# PHOTODIODE_SENSOR_NEW.net
KiCad netlist of a schematic drawn in EAGLE
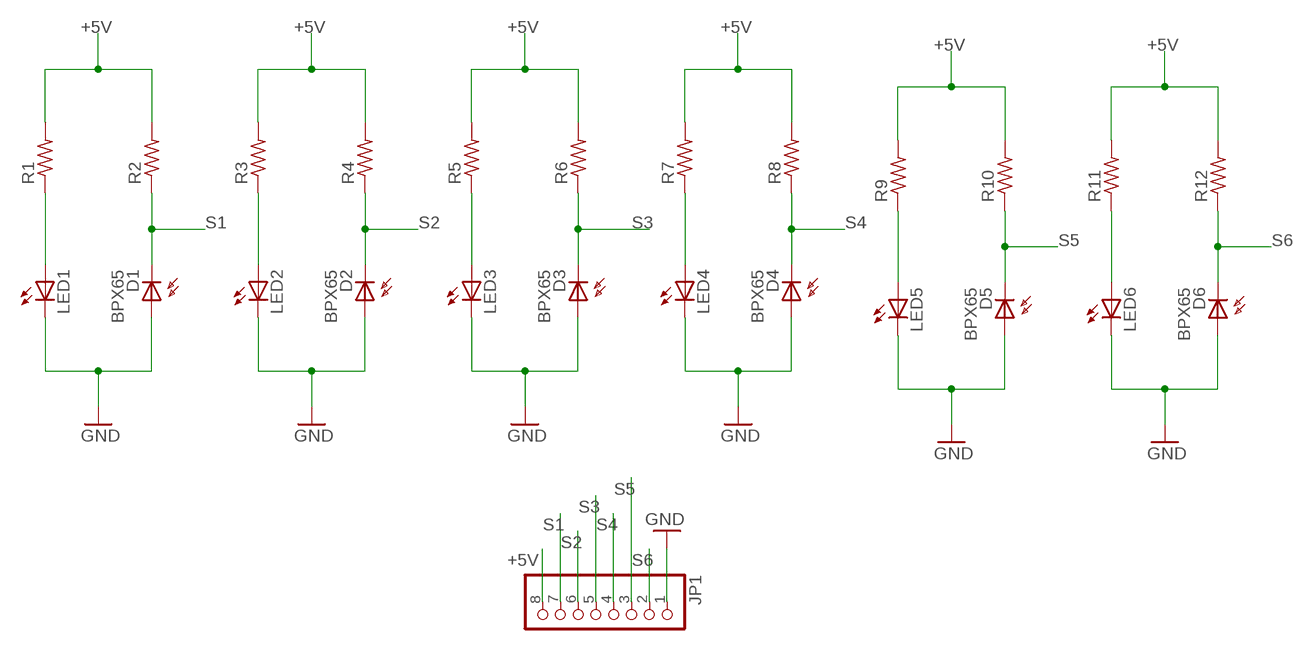
[diagram p0: schematic, sheet 1]

(export (version "E")
  (design (tool "Eeschema 10.0.6"))
  (components
    (comp (ref "D1")
      (value "BPX65")
      (footprint "eagle-import:BPX65")
      (fields (field (name "MPN") "BPX65."))
      (libsource (lib "eagle-import") (part "BPX65"))
    )
    (comp (ref "D2")
      (value "BPX65")
      (footprint "eagle-import:BPX65")
      (fields (field (name "MPN") "BPX65."))
      (libsource (lib "eagle-import") (part "BPX65"))
    )
    (comp (ref "D3")
      (value "BPX65")
      (footprint "eagle-import:BPX65")
      (fields (field (name "MPN") "BPX65."))
      (libsource (lib "eagle-import") (part "BPX65"))
    )
    (comp (ref "D4")
      (value "BPX65")
      (footprint "eagle-import:BPX65")
      (fields (field (name "MPN") "BPX65."))
      (libsource (lib "eagle-import") (part "BPX65"))
    )
    (comp (ref "D5")
      (value "BPX65")
      (footprint "eagle-import:BPX65")
      (fields (field (name "MPN") "BPX65."))
      (libsource (lib "eagle-import") (part "BPX65"))
    )
    (comp (ref "D6")
      (value "BPX65")
      (footprint "eagle-import:BPX65")
      (fields (field (name "MPN") "BPX65."))
      (libsource (lib "eagle-import") (part "BPX65"))
    )
    (comp (ref "JP1")
      (value "PINHD-1X8")
      (footprint "eagle-import:1X08")
      (libsource (lib "eagle-import") (part "PINHD-1X8"))
    )
    (comp (ref "LED1")
      (value "LED5MM")
      (footprint "eagle-import:LED5MM")
      (libsource (lib "eagle-import") (part "LED5MM"))
    )
    (comp (ref "LED2")
      (value "LED5MM")
      (footprint "eagle-import:LED5MM")
      (libsource (lib "eagle-import") (part "LED5MM"))
    )
    (comp (ref "LED3")
      (value "LED5MM")
      (footprint "eagle-import:LED5MM")
      (libsource (lib "eagle-import") (part "LED5MM"))
    )
    (comp (ref "LED4")
      (value "LED5MM")
      (footprint "eagle-import:LED5MM")
      (libsource (lib "eagle-import") (part "LED5MM"))
    )
    (comp (ref "LED5")
      (value "LED5MM")
      (footprint "eagle-import:LED5MM")
      (libsource (lib "eagle-import") (part "LED5MM"))
    )
    (comp (ref "LED6")
      (value "LED5MM")
      (footprint "eagle-import:LED5MM")
      (libsource (lib "eagle-import") (part "LED5MM"))
    )
    (comp (ref "R1")
      (value "R-US_0204/7")
      (footprint "eagle-import:0204_7")
      (libsource (lib "eagle-import") (part "R-US_0204/7"))
    )
    (comp (ref "R2")
      (value "R-US_0204/7")
      (footprint "eagle-import:0204_7")
      (libsource (lib "eagle-import") (part "R-US_0204/7"))
    )
    (comp (ref "R3")
      (value "R-US_0204/7")
      (footprint "eagle-import:0204_7")
      (libsource (lib "eagle-import") (part "R-US_0204/7"))
    )
    (comp (ref "R4")
      (value "R-US_0204/7")
      (footprint "eagle-import:0204_7")
      (libsource (lib "eagle-import") (part "R-US_0204/7"))
    )
    (comp (ref "R5")
      (value "R-US_0204/7")
      (footprint "eagle-import:0204_7")
      (libsource (lib "eagle-import") (part "R-US_0204/7"))
    )
    (comp (ref "R6")
      (value "R-US_0204/7")
      (footprint "eagle-import:0204_7")
      (libsource (lib "eagle-import") (part "R-US_0204/7"))
    )
    (comp (ref "R7")
      (value "R-US_0204/7")
      (footprint "eagle-import:0204_7")
      (libsource (lib "eagle-import") (part "R-US_0204/7"))
    )
    (comp (ref "R8")
      (value "R-US_0204/7")
      (footprint "eagle-import:0204_7")
      (libsource (lib "eagle-import") (part "R-US_0204/7"))
    )
    (comp (ref "R9")
      (value "R-US_0204/7")
      (footprint "eagle-import:0204_7")
      (libsource (lib "eagle-import") (part "R-US_0204/7"))
    )
    (comp (ref "R10")
      (value "R-US_0204/7")
      (footprint "eagle-import:0204_7")
      (libsource (lib "eagle-import") (part "R-US_0204/7"))
    )
    (comp (ref "R11")
      (value "R-US_0204/7")
      (footprint "eagle-import:0204_7")
      (libsource (lib "eagle-import") (part "R-US_0204/7"))
    )
    (comp (ref "R12")
      (value "R-US_0204/7")
      (footprint "eagle-import:0204_7")
      (libsource (lib "eagle-import") (part "R-US_0204/7"))
    )
  )
  (nets
    (net (code "1") (name "/+5V") (class "Default")
      (node (ref "JP1") (pin "8") (pinfunction "8_8") (pintype "passive"))
      (node (ref "R1") (pin "2") (pinfunction "2_2") (pintype "passive"))
      (node (ref "R10") (pin "2") (pinfunction "2_2") (pintype "passive"))
      (node (ref "R11") (pin "2") (pinfunction "2_2") (pintype "passive"))
      (node (ref "R12") (pin "2") (pinfunction "2_2") (pintype "passive"))
      (node (ref "R2") (pin "2") (pinfunction "2_2") (pintype "passive"))
      (node (ref "R3") (pin "2") (pinfunction "2_2") (pintype "passive"))
      (node (ref "R4") (pin "2") (pinfunction "2_2") (pintype "passive"))
      (node (ref "R5") (pin "2") (pinfunction "2_2") (pintype "passive"))
      (node (ref "R6") (pin "2") (pinfunction "2_2") (pintype "passive"))
      (node (ref "R7") (pin "2") (pinfunction "2_2") (pintype "passive"))
      (node (ref "R8") (pin "2") (pinfunction "2_2") (pintype "passive"))
      (node (ref "R9") (pin "2") (pinfunction "2_2") (pintype "passive"))
    )
    (net (code "2") (name "/S1") (class "Default")
      (node (ref "D1") (pin "K") (pinfunction "C_K") (pintype "passive"))
      (node (ref "JP1") (pin "7") (pinfunction "7_7") (pintype "passive"))
      (node (ref "R2") (pin "1") (pinfunction "1_1") (pintype "passive"))
    )
    (net (code "3") (name "/S2") (class "Default")
      (node (ref "D2") (pin "K") (pinfunction "C_K") (pintype "passive"))
      (node (ref "JP1") (pin "6") (pinfunction "6_6") (pintype "passive"))
      (node (ref "R4") (pin "1") (pinfunction "1_1") (pintype "passive"))
    )
    (net (code "4") (name "/S3") (class "Default")
      (node (ref "D3") (pin "K") (pinfunction "C_K") (pintype "passive"))
      (node (ref "JP1") (pin "5") (pinfunction "5_5") (pintype "passive"))
      (node (ref "R6") (pin "1") (pinfunction "1_1") (pintype "passive"))
    )
    (net (code "5") (name "/S4") (class "Default")
      (node (ref "D4") (pin "K") (pinfunction "C_K") (pintype "passive"))
      (node (ref "JP1") (pin "4") (pinfunction "4_4") (pintype "passive"))
      (node (ref "R8") (pin "1") (pinfunction "1_1") (pintype "passive"))
    )
    (net (code "6") (name "/S5") (class "Default")
      (node (ref "D5") (pin "K") (pinfunction "C_K") (pintype "passive"))
      (node (ref "JP1") (pin "3") (pinfunction "3_3") (pintype "passive"))
      (node (ref "R10") (pin "1") (pinfunction "1_1") (pintype "passive"))
    )
    (net (code "7") (name "/S6") (class "Default")
      (node (ref "D6") (pin "K") (pinfunction "C_K") (pintype "passive"))
      (node (ref "JP1") (pin "2") (pinfunction "2_2") (pintype "passive"))
      (node (ref "R12") (pin "1") (pinfunction "1_1") (pintype "passive"))
    )
    (net (code "8") (name "GND") (class "Default")
      (node (ref "D1") (pin "A") (pinfunction "A_A") (pintype "passive"))
      (node (ref "D2") (pin "A") (pinfunction "A_A") (pintype "passive"))
      (node (ref "D3") (pin "A") (pinfunction "A_A") (pintype "passive"))
      (node (ref "D4") (pin "A") (pinfunction "A_A") (pintype "passive"))
      (node (ref "D5") (pin "A") (pinfunction "A_A") (pintype "passive"))
      (node (ref "D6") (pin "A") (pinfunction "A_A") (pintype "passive"))
      (node (ref "JP1") (pin "1") (pinfunction "1_1") (pintype "passive"))
      (node (ref "LED1") (pin "K") (pinfunction "C_K") (pintype "passive"))
      (node (ref "LED2") (pin "K") (pinfunction "C_K") (pintype "passive"))
      (node (ref "LED3") (pin "K") (pinfunction "C_K") (pintype "passive"))
      (node (ref "LED4") (pin "K") (pinfunction "C_K") (pintype "passive"))
      (node (ref "LED5") (pin "K") (pinfunction "C_K") (pintype "passive"))
      (node (ref "LED6") (pin "K") (pinfunction "C_K") (pintype "passive"))
    )
    (net (code "9") (name "Net-(LED1-PadA)") (class "Default")
      (node (ref "LED1") (pin "A") (pinfunction "A_A") (pintype "passive"))
      (node (ref "R1") (pin "1") (pinfunction "1_1") (pintype "passive"))
    )
    (net (code "10") (name "Net-(LED2-PadA)") (class "Default")
      (node (ref "LED2") (pin "A") (pinfunction "A_A") (pintype "passive"))
      (node (ref "R3") (pin "1") (pinfunction "1_1") (pintype "passive"))
    )
    (net (code "11") (name "Net-(LED3-PadA)") (class "Default")
      (node (ref "LED3") (pin "A") (pinfunction "A_A") (pintype "passive"))
      (node (ref "R5") (pin "1") (pinfunction "1_1") (pintype "passive"))
    )
    (net (code "12") (name "Net-(LED4-PadA)") (class "Default")
      (node (ref "LED4") (pin "A") (pinfunction "A_A") (pintype "passive"))
      (node (ref "R7") (pin "1") (pinfunction "1_1") (pintype "passive"))
    )
    (net (code "13") (name "Net-(LED5-PadA)") (class "Default")
      (node (ref "LED5") (pin "A") (pinfunction "A_A") (pintype "passive"))
      (node (ref "R9") (pin "1") (pinfunction "1_1") (pintype "passive"))
    )
    (net (code "14") (name "Net-(LED6-PadA)") (class "Default")
      (node (ref "LED6") (pin "A") (pinfunction "A_A") (pintype "passive"))
      (node (ref "R11") (pin "1") (pinfunction "1_1") (pintype "passive"))
    )
  )
)
